# 02_Inputs_1-9.net
KiCad netlist of a schematic drawn in Altium Designer
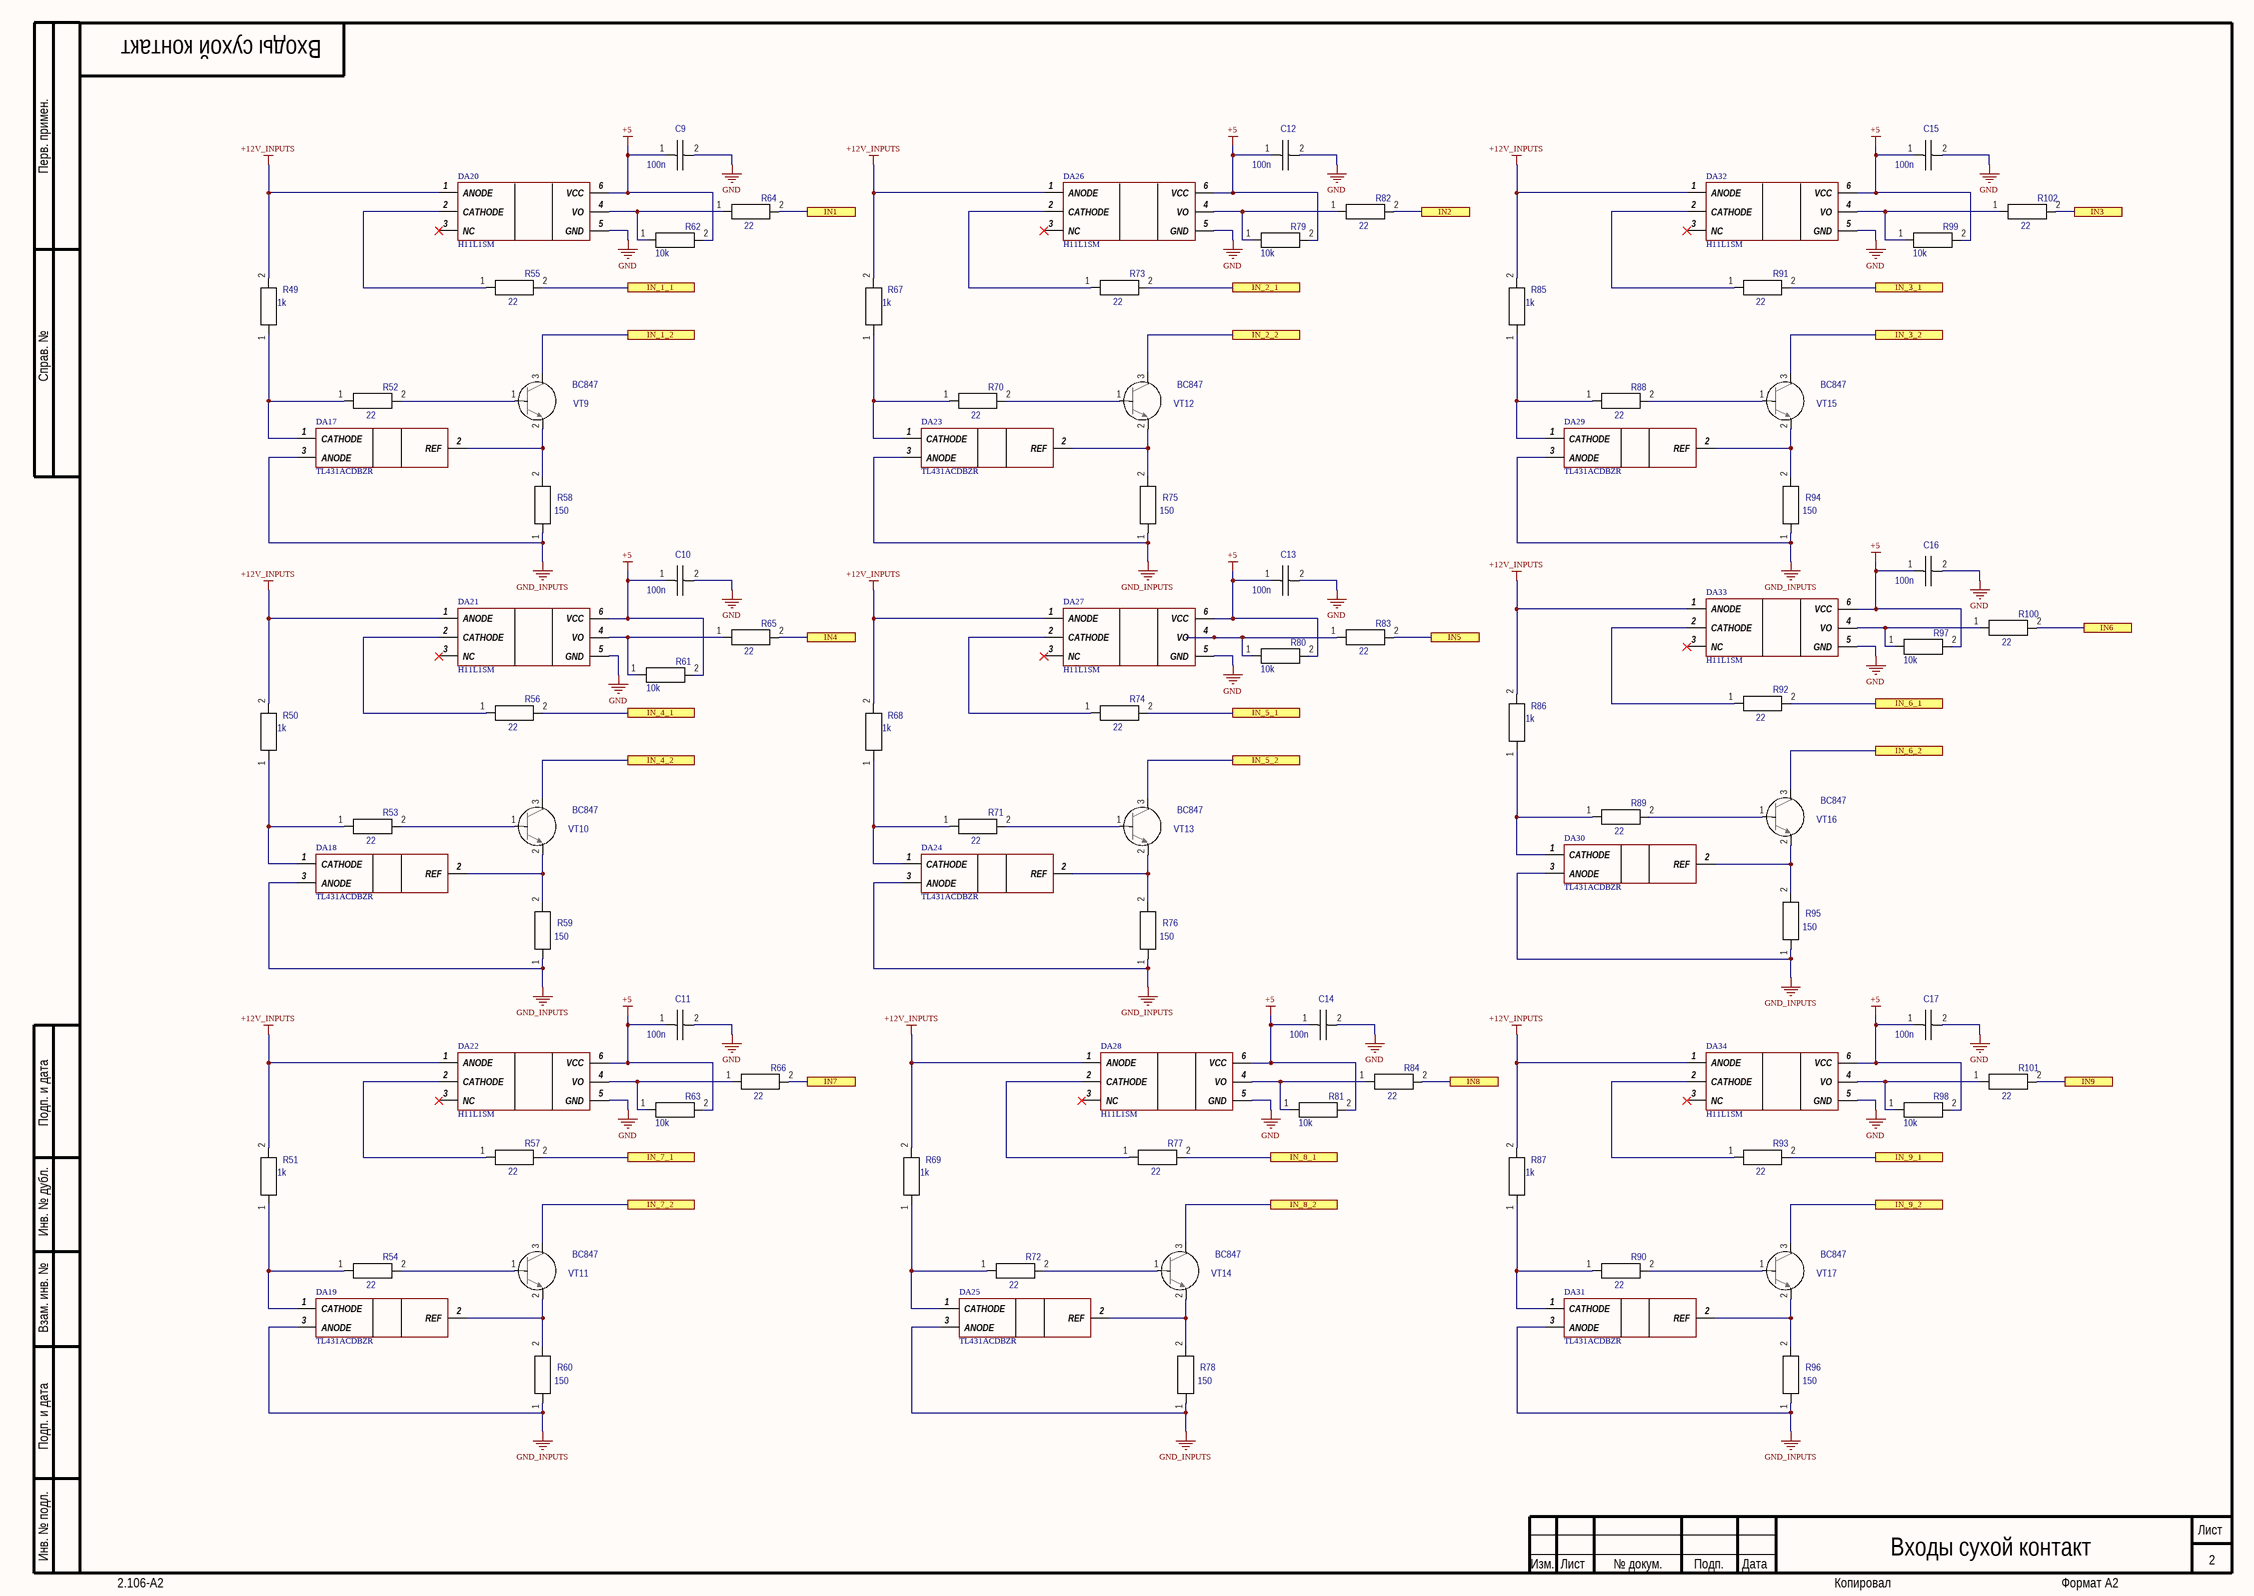
[diagram p0: 02_Inputs_1-9.SchDoc]

(export (version "E")
  (design (tool "Eeschema 10.0.6"))
  (components
    (comp (ref "C9")
      (value "100n")
      (footprint "C0603")
      (fields
        (field (name "PART NUMBER") "GRM188R71C104KA01D")
        (field (name "TOLERANCE") "±10%")
        (field (name "MANUFACTURER") "Murata Manufacturing")
      )
      (libsource (lib "AccessLibrary") (part "Capacitor"))
    )
    (comp (ref "C10")
      (value "100n")
      (footprint "C0603")
      (fields
        (field (name "PART NUMBER") "GRM188R71C104KA01D")
        (field (name "TOLERANCE") "±10%")
        (field (name "MANUFACTURER") "Murata Manufacturing")
      )
      (libsource (lib "AccessLibrary") (part "Capacitor"))
    )
    (comp (ref "C11")
      (value "100n")
      (footprint "C0603")
      (fields
        (field (name "PART NUMBER") "GRM188R71C104KA01D")
        (field (name "TOLERANCE") "±10%")
        (field (name "MANUFACTURER") "Murata Manufacturing")
      )
      (libsource (lib "AccessLibrary") (part "Capacitor"))
    )
    (comp (ref "C12")
      (value "100n")
      (footprint "C0603")
      (fields
        (field (name "PART NUMBER") "GRM188R71C104KA01D")
        (field (name "TOLERANCE") "±10%")
        (field (name "MANUFACTURER") "Murata Manufacturing")
      )
      (libsource (lib "AccessLibrary") (part "Capacitor"))
    )
    (comp (ref "C13")
      (value "100n")
      (footprint "C0603")
      (fields
        (field (name "PART NUMBER") "GRM188R71C104KA01D")
        (field (name "TOLERANCE") "±10%")
        (field (name "MANUFACTURER") "Murata Manufacturing")
      )
      (libsource (lib "AccessLibrary") (part "Capacitor"))
    )
    (comp (ref "C14")
      (value "100n")
      (footprint "C0603")
      (fields
        (field (name "PART NUMBER") "GRM188R71C104KA01D")
        (field (name "TOLERANCE") "±10%")
        (field (name "MANUFACTURER") "Murata Manufacturing")
      )
      (libsource (lib "AccessLibrary") (part "Capacitor"))
    )
    (comp (ref "C15")
      (value "100n")
      (footprint "C0603")
      (fields
        (field (name "PART NUMBER") "GRM188R71C104KA01D")
        (field (name "TOLERANCE") "±10%")
        (field (name "MANUFACTURER") "Murata Manufacturing")
      )
      (libsource (lib "AccessLibrary") (part "Capacitor"))
    )
    (comp (ref "C16")
      (value "100n")
      (footprint "C0603")
      (fields
        (field (name "PART NUMBER") "GRM188R71C104KA01D")
        (field (name "TOLERANCE") "±10%")
        (field (name "MANUFACTURER") "Murata Manufacturing")
      )
      (libsource (lib "AccessLibrary") (part "Capacitor"))
    )
    (comp (ref "C17")
      (value "100n")
      (footprint "C0603")
      (fields
        (field (name "PART NUMBER") "GRM188R71C104KA01D")
        (field (name "TOLERANCE") "±10%")
        (field (name "MANUFACTURER") "Murata Manufacturing")
      )
      (libsource (lib "AccessLibrary") (part "Capacitor"))
    )
    (comp (ref "DA17")
      (value "TL431ACDBZR")
      (footprint "board:SOT95P237X112-3N")
      (description "Integrated Circuit")
      (fields (field (name "MOUSER PART NUMBER") "595-TL431ACDBZR"))
      (libsource (lib "board") (part "TL431ACDBZR"))
    )
    (comp (ref "DA18")
      (value "TL431ACDBZR")
      (footprint "board:SOT95P237X112-3N")
      (description "Integrated Circuit")
      (fields (field (name "MOUSER PART NUMBER") "595-TL431ACDBZR"))
      (libsource (lib "board") (part "TL431ACDBZR"))
    )
    (comp (ref "DA19")
      (value "TL431ACDBZR")
      (footprint "board:SOT95P237X112-3N")
      (description "Integrated Circuit")
      (fields (field (name "MOUSER PART NUMBER") "595-TL431ACDBZR"))
      (libsource (lib "board") (part "TL431ACDBZR"))
    )
    (comp (ref "DA20")
      (value "H11L1SM")
      (footprint "board:SOP254P1030X460-6N")
      (description "Integrated Circuit")
      (libsource (lib "board") (part "H11L1SM"))
    )
    (comp (ref "DA21")
      (value "H11L1SM")
      (footprint "board:SOP254P1030X460-6N")
      (description "Integrated Circuit")
      (libsource (lib "board") (part "H11L1SM"))
    )
    (comp (ref "DA22")
      (value "H11L1SM")
      (footprint "board:SOP254P1030X460-6N")
      (description "Integrated Circuit")
      (libsource (lib "board") (part "H11L1SM"))
    )
    (comp (ref "DA23")
      (value "TL431ACDBZR")
      (footprint "board:SOT95P237X112-3N")
      (description "Integrated Circuit")
      (fields (field (name "MOUSER PART NUMBER") "595-TL431ACDBZR"))
      (libsource (lib "board") (part "TL431ACDBZR"))
    )
    (comp (ref "DA24")
      (value "TL431ACDBZR")
      (footprint "board:SOT95P237X112-3N")
      (description "Integrated Circuit")
      (fields (field (name "MOUSER PART NUMBER") "595-TL431ACDBZR"))
      (libsource (lib "board") (part "TL431ACDBZR"))
    )
    (comp (ref "DA25")
      (value "TL431ACDBZR")
      (footprint "board:SOT95P237X112-3N")
      (description "Integrated Circuit")
      (fields (field (name "MOUSER PART NUMBER") "595-TL431ACDBZR"))
      (libsource (lib "board") (part "TL431ACDBZR"))
    )
    (comp (ref "DA26")
      (value "H11L1SM")
      (footprint "board:SOP254P1030X460-6N")
      (description "Integrated Circuit")
      (libsource (lib "board") (part "H11L1SM"))
    )
    (comp (ref "DA27")
      (value "H11L1SM")
      (footprint "board:SOP254P1030X460-6N")
      (description "Integrated Circuit")
      (libsource (lib "board") (part "H11L1SM"))
    )
    (comp (ref "DA28")
      (value "H11L1SM")
      (footprint "board:SOP254P1030X460-6N")
      (description "Integrated Circuit")
      (libsource (lib "board") (part "H11L1SM"))
    )
    (comp (ref "DA29")
      (value "TL431ACDBZR")
      (footprint "board:SOT95P237X112-3N")
      (description "Integrated Circuit")
      (fields (field (name "MOUSER PART NUMBER") "595-TL431ACDBZR"))
      (libsource (lib "board") (part "TL431ACDBZR"))
    )
    (comp (ref "DA30")
      (value "TL431ACDBZR")
      (footprint "board:SOT95P237X112-3N")
      (description "Integrated Circuit")
      (fields (field (name "MOUSER PART NUMBER") "595-TL431ACDBZR"))
      (libsource (lib "board") (part "TL431ACDBZR"))
    )
    (comp (ref "DA31")
      (value "TL431ACDBZR")
      (footprint "board:SOT95P237X112-3N")
      (description "Integrated Circuit")
      (fields (field (name "MOUSER PART NUMBER") "595-TL431ACDBZR"))
      (libsource (lib "board") (part "TL431ACDBZR"))
    )
    (comp (ref "DA32")
      (value "H11L1SM")
      (footprint "board:SOP254P1030X460-6N")
      (description "Integrated Circuit")
      (libsource (lib "board") (part "H11L1SM"))
    )
    (comp (ref "DA33")
      (value "H11L1SM")
      (footprint "board:SOP254P1030X460-6N")
      (description "Integrated Circuit")
      (libsource (lib "board") (part "H11L1SM"))
    )
    (comp (ref "DA34")
      (value "H11L1SM")
      (footprint "board:SOP254P1030X460-6N")
      (description "Integrated Circuit")
      (libsource (lib "board") (part "H11L1SM"))
    )
    (comp (ref "R49")
      (value "1k")
      (footprint "RESC1608N")
      (fields
        (field (name "PART NUMBER") "RC0603FK-071KL")
        (field (name "TOLERANCE") "±1%")
        (field (name "MANUFACTURER") "Тайвань")
      )
      (libsource (lib "AccessLibrary") (part "Resistor"))
    )
    (comp (ref "R50")
      (value "1k")
      (footprint "RESC1608N")
      (fields
        (field (name "PART NUMBER") "RC0603FK-071KL")
        (field (name "TOLERANCE") "±1%")
        (field (name "MANUFACTURER") "Тайвань")
      )
      (libsource (lib "AccessLibrary") (part "Resistor"))
    )
    (comp (ref "R51")
      (value "1k")
      (footprint "RESC1608N")
      (fields
        (field (name "PART NUMBER") "RC0603FK-071KL")
        (field (name "TOLERANCE") "±1%")
        (field (name "MANUFACTURER") "Тайвань")
      )
      (libsource (lib "AccessLibrary") (part "Resistor"))
    )
    (comp (ref "R52")
      (value "22")
      (footprint "RESC1608N")
      (fields
        (field (name "PART NUMBER") "RC0603FK-0722RL")
        (field (name "TOLERANCE") "±1%")
        (field (name "MANUFACTURER") "Тайвань")
      )
      (libsource (lib "AccessLibrary") (part "Resistor"))
    )
    (comp (ref "R53")
      (value "22")
      (footprint "RESC1608N")
      (fields
        (field (name "PART NUMBER") "RC0603FK-0722RL")
        (field (name "TOLERANCE") "±1%")
        (field (name "MANUFACTURER") "Тайвань")
      )
      (libsource (lib "AccessLibrary") (part "Resistor"))
    )
    (comp (ref "R54")
      (value "22")
      (footprint "RESC1608N")
      (fields
        (field (name "PART NUMBER") "RC0603FK-0722RL")
        (field (name "TOLERANCE") "±1%")
        (field (name "MANUFACTURER") "Тайвань")
      )
      (libsource (lib "AccessLibrary") (part "Resistor"))
    )
    (comp (ref "R55")
      (value "22")
      (footprint "RESC1608N")
      (fields
        (field (name "PART NUMBER") "RC0603FK-0722RL")
        (field (name "TOLERANCE") "±1%")
        (field (name "MANUFACTURER") "Тайвань")
      )
      (libsource (lib "AccessLibrary") (part "Resistor"))
    )
    (comp (ref "R56")
      (value "22")
      (footprint "RESC1608N")
      (fields
        (field (name "PART NUMBER") "RC0603FK-0722RL")
        (field (name "TOLERANCE") "±1%")
        (field (name "MANUFACTURER") "Тайвань")
      )
      (libsource (lib "AccessLibrary") (part "Resistor"))
    )
    (comp (ref "R57")
      (value "22")
      (footprint "RESC1608N")
      (fields
        (field (name "PART NUMBER") "RC0603FK-0722RL")
        (field (name "TOLERANCE") "±1%")
        (field (name "MANUFACTURER") "Тайвань")
      )
      (libsource (lib "AccessLibrary") (part "Resistor"))
    )
    (comp (ref "R58")
      (value "150")
      (footprint "RESC1608N")
      (fields
        (field (name "PART NUMBER") "RC0603FK-07150RL")
        (field (name "TOLERANCE") "±1%")
        (field (name "MANUFACTURER") "Тайвань")
      )
      (libsource (lib "AccessLibrary") (part "Resistor"))
    )
    (comp (ref "R59")
      (value "150")
      (footprint "RESC1608N")
      (fields
        (field (name "PART NUMBER") "RC0603FK-07150RL")
        (field (name "TOLERANCE") "±1%")
        (field (name "MANUFACTURER") "Тайвань")
      )
      (libsource (lib "AccessLibrary") (part "Resistor"))
    )
    (comp (ref "R60")
      (value "150")
      (footprint "RESC1608N")
      (fields
        (field (name "PART NUMBER") "RC0603FK-07150RL")
        (field (name "TOLERANCE") "±1%")
        (field (name "MANUFACTURER") "Тайвань")
      )
      (libsource (lib "AccessLibrary") (part "Resistor"))
    )
    (comp (ref "R61")
      (value "10k")
      (footprint "RESC1608N")
      (fields
        (field (name "PART NUMBER") "RC0603FR-0710KL")
        (field (name "TOLERANCE") "±1%")
        (field (name "MANUFACTURER") "Тайвань")
      )
      (libsource (lib "AccessLibrary") (part "Resistor"))
    )
    (comp (ref "R62")
      (value "10k")
      (footprint "RESC1608N")
      (fields
        (field (name "PART NUMBER") "RC0603FR-0710KL")
        (field (name "TOLERANCE") "±1%")
        (field (name "MANUFACTURER") "Тайвань")
      )
      (libsource (lib "AccessLibrary") (part "Resistor"))
    )
    (comp (ref "R63")
      (value "10k")
      (footprint "RESC1608N")
      (fields
        (field (name "PART NUMBER") "RC0603FR-0710KL")
        (field (name "TOLERANCE") "±1%")
        (field (name "MANUFACTURER") "Тайвань")
      )
      (libsource (lib "AccessLibrary") (part "Resistor"))
    )
    (comp (ref "R64")
      (value "22")
      (footprint "RESC1608N")
      (fields
        (field (name "PART NUMBER") "RC0603FK-0722RL")
        (field (name "TOLERANCE") "±1%")
        (field (name "MANUFACTURER") "Тайвань")
      )
      (libsource (lib "AccessLibrary") (part "Resistor"))
    )
    (comp (ref "R65")
      (value "22")
      (footprint "RESC1608N")
      (fields
        (field (name "PART NUMBER") "RC0603FK-0722RL")
        (field (name "TOLERANCE") "±1%")
        (field (name "MANUFACTURER") "Тайвань")
      )
      (libsource (lib "AccessLibrary") (part "Resistor"))
    )
    (comp (ref "R66")
      (value "22")
      (footprint "RESC1608N")
      (fields
        (field (name "PART NUMBER") "RC0603FK-0722RL")
        (field (name "TOLERANCE") "±1%")
        (field (name "MANUFACTURER") "Тайвань")
      )
      (libsource (lib "AccessLibrary") (part "Resistor"))
    )
    (comp (ref "R67")
      (value "1k")
      (footprint "RESC1608N")
      (fields
        (field (name "PART NUMBER") "RC0603FK-071KL")
        (field (name "TOLERANCE") "±1%")
        (field (name "MANUFACTURER") "Тайвань")
      )
      (libsource (lib "AccessLibrary") (part "Resistor"))
    )
    (comp (ref "R68")
      (value "1k")
      (footprint "RESC1608N")
      (fields
        (field (name "PART NUMBER") "RC0603FK-071KL")
        (field (name "TOLERANCE") "±1%")
        (field (name "MANUFACTURER") "Тайвань")
      )
      (libsource (lib "AccessLibrary") (part "Resistor"))
    )
    (comp (ref "R69")
      (value "1k")
      (footprint "RESC1608N")
      (fields
        (field (name "PART NUMBER") "RC0603FK-071KL")
        (field (name "TOLERANCE") "±1%")
        (field (name "MANUFACTURER") "Тайвань")
      )
      (libsource (lib "AccessLibrary") (part "Resistor"))
    )
    (comp (ref "R70")
      (value "22")
      (footprint "RESC1608N")
      (fields
        (field (name "PART NUMBER") "RC0603FK-0722RL")
        (field (name "TOLERANCE") "±1%")
        (field (name "MANUFACTURER") "Тайвань")
      )
      (libsource (lib "AccessLibrary") (part "Resistor"))
    )
    (comp (ref "R71")
      (value "22")
      (footprint "RESC1608N")
      (fields
        (field (name "PART NUMBER") "RC0603FK-0722RL")
        (field (name "TOLERANCE") "±1%")
        (field (name "MANUFACTURER") "Тайвань")
      )
      (libsource (lib "AccessLibrary") (part "Resistor"))
    )
    (comp (ref "R72")
      (value "22")
      (footprint "RESC1608N")
      (fields
        (field (name "PART NUMBER") "RC0603FK-0722RL")
        (field (name "TOLERANCE") "±1%")
        (field (name "MANUFACTURER") "Тайвань")
      )
      (libsource (lib "AccessLibrary") (part "Resistor"))
    )
    (comp (ref "R73")
      (value "22")
      (footprint "RESC1608N")
      (fields
        (field (name "PART NUMBER") "RC0603FK-0722RL")
        (field (name "TOLERANCE") "±1%")
        (field (name "MANUFACTURER") "Тайвань")
      )
      (libsource (lib "AccessLibrary") (part "Resistor"))
    )
    (comp (ref "R74")
      (value "22")
      (footprint "RESC1608N")
      (fields
        (field (name "PART NUMBER") "RC0603FK-0722RL")
        (field (name "TOLERANCE") "±1%")
        (field (name "MANUFACTURER") "Тайвань")
      )
      (libsource (lib "AccessLibrary") (part "Resistor"))
    )
    (comp (ref "R75")
      (value "150")
      (footprint "RESC1608N")
      (fields
        (field (name "PART NUMBER") "RC0603FK-07150RL")
        (field (name "TOLERANCE") "±1%")
        (field (name "MANUFACTURER") "Тайвань")
      )
      (libsource (lib "AccessLibrary") (part "Resistor"))
    )
    (comp (ref "R76")
      (value "150")
      (footprint "RESC1608N")
      (fields
        (field (name "PART NUMBER") "RC0603FK-07150RL")
        (field (name "TOLERANCE") "±1%")
        (field (name "MANUFACTURER") "Тайвань")
      )
      (libsource (lib "AccessLibrary") (part "Resistor"))
    )
    (comp (ref "R77")
      (value "22")
      (footprint "RESC1608N")
      (fields
        (field (name "PART NUMBER") "RC0603FK-0722RL")
        (field (name "TOLERANCE") "±1%")
        (field (name "MANUFACTURER") "Тайвань")
      )
      (libsource (lib "AccessLibrary") (part "Resistor"))
    )
    (comp (ref "R78")
      (value "150")
      (footprint "RESC1608N")
      (fields
        (field (name "PART NUMBER") "RC0603FK-07150RL")
        (field (name "TOLERANCE") "±1%")
        (field (name "MANUFACTURER") "Тайвань")
      )
      (libsource (lib "AccessLibrary") (part "Resistor"))
    )
    (comp (ref "R79")
      (value "10k")
      (footprint "RESC1608N")
      (fields
        (field (name "PART NUMBER") "RC0603FR-0710KL")
        (field (name "TOLERANCE") "±1%")
        (field (name "MANUFACTURER") "Тайвань")
      )
      (libsource (lib "AccessLibrary") (part "Resistor"))
    )
    (comp (ref "R80")
      (value "10k")
      (footprint "RESC1608N")
      (fields
        (field (name "PART NUMBER") "RC0603FR-0710KL")
        (field (name "TOLERANCE") "±1%")
        (field (name "MANUFACTURER") "Тайвань")
      )
      (libsource (lib "AccessLibrary") (part "Resistor"))
    )
    (comp (ref "R81")
      (value "10k")
      (footprint "RESC1608N")
      (fields
        (field (name "PART NUMBER") "RC0603FR-0710KL")
        (field (name "TOLERANCE") "±1%")
        (field (name "MANUFACTURER") "Тайвань")
      )
      (libsource (lib "AccessLibrary") (part "Resistor"))
    )
    (comp (ref "R82")
      (value "22")
      (footprint "RESC1608N")
      (fields
        (field (name "PART NUMBER") "RC0603FK-0722RL")
        (field (name "TOLERANCE") "±1%")
        (field (name "MANUFACTURER") "Тайвань")
      )
      (libsource (lib "AccessLibrary") (part "Resistor"))
    )
    (comp (ref "R83")
      (value "22")
      (footprint "RESC1608N")
      (fields
        (field (name "PART NUMBER") "RC0603FK-0722RL")
        (field (name "TOLERANCE") "±1%")
        (field (name "MANUFACTURER") "Тайвань")
      )
      (libsource (lib "AccessLibrary") (part "Resistor"))
    )
    (comp (ref "R84")
      (value "22")
      (footprint "RESC1608N")
      (fields
        (field (name "PART NUMBER") "RC0603FK-0722RL")
        (field (name "TOLERANCE") "±1%")
        (field (name "MANUFACTURER") "Тайвань")
      )
      (libsource (lib "AccessLibrary") (part "Resistor"))
    )
    (comp (ref "R85")
      (value "1k")
      (footprint "RESC1608N")
      (fields
        (field (name "PART NUMBER") "RC0603FK-071KL")
        (field (name "TOLERANCE") "±1%")
        (field (name "MANUFACTURER") "Тайвань")
      )
      (libsource (lib "AccessLibrary") (part "Resistor"))
    )
    (comp (ref "R86")
      (value "1k")
      (footprint "RESC1608N")
      (fields
        (field (name "PART NUMBER") "RC0603FK-071KL")
        (field (name "TOLERANCE") "±1%")
        (field (name "MANUFACTURER") "Тайвань")
      )
      (libsource (lib "AccessLibrary") (part "Resistor"))
    )
    (comp (ref "R87")
      (value "1k")
      (footprint "RESC1608N")
      (fields
        (field (name "PART NUMBER") "RC0603FK-071KL")
        (field (name "TOLERANCE") "±1%")
        (field (name "MANUFACTURER") "Тайвань")
      )
      (libsource (lib "AccessLibrary") (part "Resistor"))
    )
    (comp (ref "R88")
      (value "22")
      (footprint "RESC1608N")
      (fields
        (field (name "PART NUMBER") "RC0603FK-0722RL")
        (field (name "TOLERANCE") "±1%")
        (field (name "MANUFACTURER") "Тайвань")
      )
      (libsource (lib "AccessLibrary") (part "Resistor"))
    )
    (comp (ref "R89")
      (value "22")
      (footprint "RESC1608N")
      (fields
        (field (name "PART NUMBER") "RC0603FK-0722RL")
        (field (name "TOLERANCE") "±1%")
        (field (name "MANUFACTURER") "Тайвань")
      )
      (libsource (lib "AccessLibrary") (part "Resistor"))
    )
    (comp (ref "R90")
      (value "22")
      (footprint "RESC1608N")
      (fields
        (field (name "PART NUMBER") "RC0603FK-0722RL")
        (field (name "TOLERANCE") "±1%")
        (field (name "MANUFACTURER") "Тайвань")
      )
      (libsource (lib "AccessLibrary") (part "Resistor"))
    )
    (comp (ref "R91")
      (value "22")
      (footprint "RESC1608N")
      (fields
        (field (name "PART NUMBER") "RC0603FK-0722RL")
        (field (name "TOLERANCE") "±1%")
        (field (name "MANUFACTURER") "Тайвань")
      )
      (libsource (lib "AccessLibrary") (part "Resistor"))
    )
    (comp (ref "R92")
      (value "22")
      (footprint "RESC1608N")
      (fields
        (field (name "PART NUMBER") "RC0603FK-0722RL")
        (field (name "TOLERANCE") "±1%")
        (field (name "MANUFACTURER") "Тайвань")
      )
      (libsource (lib "AccessLibrary") (part "Resistor"))
    )
    (comp (ref "R93")
      (value "22")
      (footprint "RESC1608N")
      (fields
        (field (name "PART NUMBER") "RC0603FK-0722RL")
        (field (name "TOLERANCE") "±1%")
        (field (name "MANUFACTURER") "Тайвань")
      )
      (libsource (lib "AccessLibrary") (part "Resistor"))
    )
    (comp (ref "R94")
      (value "150")
      (footprint "RESC1608N")
      (fields
        (field (name "PART NUMBER") "RC0603FK-07150RL")
        (field (name "TOLERANCE") "±1%")
        (field (name "MANUFACTURER") "Тайвань")
      )
      (libsource (lib "AccessLibrary") (part "Resistor"))
    )
    (comp (ref "R95")
      (value "150")
      (footprint "RESC1608N")
      (fields
        (field (name "PART NUMBER") "RC0603FK-07150RL")
        (field (name "TOLERANCE") "±1%")
        (field (name "MANUFACTURER") "Тайвань")
      )
      (libsource (lib "AccessLibrary") (part "Resistor"))
    )
    (comp (ref "R96")
      (value "150")
      (footprint "RESC1608N")
      (fields
        (field (name "PART NUMBER") "RC0603FK-07150RL")
        (field (name "TOLERANCE") "±1%")
        (field (name "MANUFACTURER") "Тайвань")
      )
      (libsource (lib "AccessLibrary") (part "Resistor"))
    )
    (comp (ref "R97")
      (value "10k")
      (footprint "RESC1608N")
      (fields
        (field (name "PART NUMBER") "RC0603FR-0710KL")
        (field (name "TOLERANCE") "±1%")
        (field (name "MANUFACTURER") "Тайвань")
      )
      (libsource (lib "AccessLibrary") (part "Resistor"))
    )
    (comp (ref "R98")
      (value "10k")
      (footprint "RESC1608N")
      (fields
        (field (name "PART NUMBER") "RC0603FR-0710KL")
        (field (name "TOLERANCE") "±1%")
        (field (name "MANUFACTURER") "Тайвань")
      )
      (libsource (lib "AccessLibrary") (part "Resistor"))
    )
    (comp (ref "R99")
      (value "10k")
      (footprint "RESC1608N")
      (fields
        (field (name "PART NUMBER") "RC0603FR-0710KL")
        (field (name "TOLERANCE") "±1%")
        (field (name "MANUFACTURER") "Тайвань")
      )
      (libsource (lib "AccessLibrary") (part "Resistor"))
    )
    (comp (ref "R100")
      (value "22")
      (footprint "RESC1608N")
      (fields
        (field (name "PART NUMBER") "RC0603FK-0722RL")
        (field (name "TOLERANCE") "±1%")
        (field (name "MANUFACTURER") "Тайвань")
      )
      (libsource (lib "AccessLibrary") (part "Resistor"))
    )
    (comp (ref "R101")
      (value "22")
      (footprint "RESC1608N")
      (fields
        (field (name "PART NUMBER") "RC0603FK-0722RL")
        (field (name "TOLERANCE") "±1%")
        (field (name "MANUFACTURER") "Тайвань")
      )
      (libsource (lib "AccessLibrary") (part "Resistor"))
    )
    (comp (ref "R102")
      (value "22")
      (footprint "RESC1608N")
      (fields
        (field (name "PART NUMBER") "RC0603FK-0722RL")
        (field (name "TOLERANCE") "±1%")
        (field (name "MANUFACTURER") "Тайвань")
      )
      (libsource (lib "AccessLibrary") (part "Resistor"))
    )
    (comp (ref "VT9")
      (value "BC847")
      (footprint "SOT23-3N")
      (fields (field (name "COM") "BC847") (field (name "MANUFACTURER") "NXP Semiconductor"))
      (libsource (lib "AccessLibrary") (part "Transistor_npn_1b-2e-3c"))
    )
    (comp (ref "VT10")
      (value "BC847")
      (footprint "SOT23-3N")
      (fields (field (name "COM") "BC847") (field (name "MANUFACTURER") "NXP Semiconductor"))
      (libsource (lib "AccessLibrary") (part "Transistor_npn_1b-2e-3c"))
    )
    (comp (ref "VT11")
      (value "BC847")
      (footprint "SOT23-3N")
      (fields (field (name "COM") "BC847") (field (name "MANUFACTURER") "NXP Semiconductor"))
      (libsource (lib "AccessLibrary") (part "Transistor_npn_1b-2e-3c"))
    )
    (comp (ref "VT12")
      (value "BC847")
      (footprint "SOT23-3N")
      (fields (field (name "COM") "BC847") (field (name "MANUFACTURER") "NXP Semiconductor"))
      (libsource (lib "AccessLibrary") (part "Transistor_npn_1b-2e-3c"))
    )
    (comp (ref "VT13")
      (value "BC847")
      (footprint "SOT23-3N")
      (fields (field (name "COM") "BC847") (field (name "MANUFACTURER") "NXP Semiconductor"))
      (libsource (lib "AccessLibrary") (part "Transistor_npn_1b-2e-3c"))
    )
    (comp (ref "VT14")
      (value "BC847")
      (footprint "SOT23-3N")
      (fields (field (name "COM") "BC847") (field (name "MANUFACTURER") "NXP Semiconductor"))
      (libsource (lib "AccessLibrary") (part "Transistor_npn_1b-2e-3c"))
    )
    (comp (ref "VT15")
      (value "BC847")
      (footprint "SOT23-3N")
      (fields (field (name "COM") "BC847") (field (name "MANUFACTURER") "NXP Semiconductor"))
      (libsource (lib "AccessLibrary") (part "Transistor_npn_1b-2e-3c"))
    )
    (comp (ref "VT16")
      (value "BC847")
      (footprint "SOT23-3N")
      (fields (field (name "COM") "BC847") (field (name "MANUFACTURER") "NXP Semiconductor"))
      (libsource (lib "AccessLibrary") (part "Transistor_npn_1b-2e-3c"))
    )
    (comp (ref "VT17")
      (value "BC847")
      (footprint "SOT23-3N")
      (fields (field (name "COM") "BC847") (field (name "MANUFACTURER") "NXP Semiconductor"))
      (libsource (lib "AccessLibrary") (part "Transistor_npn_1b-2e-3c"))
    )
  )
  (nets
    (net (code "1") (name "+5") (class "Default")
      (node (ref "C10") (pin "1") (pinfunction "1_1") (pintype "passive"))
      (node (ref "C11") (pin "1") (pinfunction "1_1") (pintype "passive"))
      (node (ref "C12") (pin "1") (pinfunction "1_1") (pintype "passive"))
      (node (ref "C13") (pin "1") (pinfunction "1_1") (pintype "passive"))
      (node (ref "C14") (pin "1") (pinfunction "1_1") (pintype "passive"))
      (node (ref "C15") (pin "1") (pinfunction "1_1") (pintype "passive"))
      (node (ref "C16") (pin "1") (pinfunction "1_1") (pintype "passive"))
      (node (ref "C17") (pin "1") (pinfunction "1_1") (pintype "passive"))
      (node (ref "C9") (pin "1") (pinfunction "1_1") (pintype "passive"))
      (node (ref "DA20") (pin "6") (pinfunction "VCC_6") (pintype "passive"))
      (node (ref "DA21") (pin "6") (pinfunction "VCC_6") (pintype "passive"))
      (node (ref "DA22") (pin "6") (pinfunction "VCC_6") (pintype "passive"))
      (node (ref "DA26") (pin "6") (pinfunction "VCC_6") (pintype "passive"))
      (node (ref "DA27") (pin "6") (pinfunction "VCC_6") (pintype "passive"))
      (node (ref "DA28") (pin "6") (pinfunction "VCC_6") (pintype "passive"))
      (node (ref "DA32") (pin "6") (pinfunction "VCC_6") (pintype "passive"))
      (node (ref "DA33") (pin "6") (pinfunction "VCC_6") (pintype "passive"))
      (node (ref "DA34") (pin "6") (pinfunction "VCC_6") (pintype "passive"))
      (node (ref "R61") (pin "2") (pinfunction "2_2") (pintype "passive"))
      (node (ref "R62") (pin "2") (pinfunction "2_2") (pintype "passive"))
      (node (ref "R63") (pin "2") (pinfunction "2_2") (pintype "passive"))
      (node (ref "R79") (pin "2") (pinfunction "2_2") (pintype "passive"))
      (node (ref "R80") (pin "2") (pinfunction "2_2") (pintype "passive"))
      (node (ref "R81") (pin "2") (pinfunction "2_2") (pintype "passive"))
      (node (ref "R97") (pin "2") (pinfunction "2_2") (pintype "passive"))
      (node (ref "R98") (pin "2") (pinfunction "2_2") (pintype "passive"))
      (node (ref "R99") (pin "2") (pinfunction "2_2") (pintype "passive"))
    )
    (net (code "2") (name "+12V_INPUTS") (class "Default")
      (node (ref "DA20") (pin "1") (pinfunction "ANODE_1") (pintype "passive"))
      (node (ref "DA21") (pin "1") (pinfunction "ANODE_1") (pintype "passive"))
      (node (ref "DA22") (pin "1") (pinfunction "ANODE_1") (pintype "passive"))
      (node (ref "DA26") (pin "1") (pinfunction "ANODE_1") (pintype "passive"))
      (node (ref "DA27") (pin "1") (pinfunction "ANODE_1") (pintype "passive"))
      (node (ref "DA28") (pin "1") (pinfunction "ANODE_1") (pintype "passive"))
      (node (ref "DA32") (pin "1") (pinfunction "ANODE_1") (pintype "passive"))
      (node (ref "DA33") (pin "1") (pinfunction "ANODE_1") (pintype "passive"))
      (node (ref "DA34") (pin "1") (pinfunction "ANODE_1") (pintype "passive"))
      (node (ref "R49") (pin "2") (pinfunction "2_2") (pintype "passive"))
      (node (ref "R50") (pin "2") (pinfunction "2_2") (pintype "passive"))
      (node (ref "R51") (pin "2") (pinfunction "2_2") (pintype "passive"))
      (node (ref "R67") (pin "2") (pinfunction "2_2") (pintype "passive"))
      (node (ref "R68") (pin "2") (pinfunction "2_2") (pintype "passive"))
      (node (ref "R69") (pin "2") (pinfunction "2_2") (pintype "passive"))
      (node (ref "R85") (pin "2") (pinfunction "2_2") (pintype "passive"))
      (node (ref "R86") (pin "2") (pinfunction "2_2") (pintype "passive"))
      (node (ref "R87") (pin "2") (pinfunction "2_2") (pintype "passive"))
    )
    (net (code "3") (name "/IN1") (class "Default")
      (node (ref "R64") (pin "2") (pinfunction "2_2") (pintype "passive"))
    )
    (net (code "4") (name "/IN2") (class "Default")
      (node (ref "R82") (pin "2") (pinfunction "2_2") (pintype "passive"))
    )
    (net (code "5") (name "/IN3") (class "Default")
      (node (ref "R102") (pin "2") (pinfunction "2_2") (pintype "passive"))
    )
    (net (code "6") (name "/IN4") (class "Default")
      (node (ref "R65") (pin "2") (pinfunction "2_2") (pintype "passive"))
    )
    (net (code "7") (name "/IN5") (class "Default")
      (node (ref "R83") (pin "2") (pinfunction "2_2") (pintype "passive"))
    )
    (net (code "8") (name "/IN6") (class "Default")
      (node (ref "R100") (pin "2") (pinfunction "2_2") (pintype "passive"))
    )
    (net (code "9") (name "/IN7") (class "Default")
      (node (ref "R66") (pin "2") (pinfunction "2_2") (pintype "passive"))
    )
    (net (code "10") (name "/IN8") (class "Default")
      (node (ref "R84") (pin "2") (pinfunction "2_2") (pintype "passive"))
    )
    (net (code "11") (name "/IN9") (class "Default")
      (node (ref "R101") (pin "2") (pinfunction "2_2") (pintype "passive"))
    )
    (net (code "12") (name "/IN_1_1") (class "Default")
      (node (ref "R55") (pin "2") (pinfunction "2_2") (pintype "passive"))
    )
    (net (code "13") (name "/IN_1_2") (class "Default")
      (node (ref "VT9") (pin "3") (pinfunction "3_3") (pintype "passive"))
    )
    (net (code "14") (name "/IN_2_1") (class "Default")
      (node (ref "R73") (pin "2") (pinfunction "2_2") (pintype "passive"))
    )
    (net (code "15") (name "/IN_2_2") (class "Default")
      (node (ref "VT12") (pin "3") (pinfunction "3_3") (pintype "passive"))
    )
    (net (code "16") (name "/IN_3_1") (class "Default")
      (node (ref "R91") (pin "2") (pinfunction "2_2") (pintype "passive"))
    )
    (net (code "17") (name "/IN_3_2") (class "Default")
      (node (ref "VT15") (pin "3") (pinfunction "3_3") (pintype "passive"))
    )
    (net (code "18") (name "/IN_4_1") (class "Default")
      (node (ref "R56") (pin "2") (pinfunction "2_2") (pintype "passive"))
    )
    (net (code "19") (name "/IN_4_2") (class "Default")
      (node (ref "VT10") (pin "3") (pinfunction "3_3") (pintype "passive"))
    )
    (net (code "20") (name "/IN_5_1") (class "Default")
      (node (ref "R74") (pin "2") (pinfunction "2_2") (pintype "passive"))
    )
    (net (code "21") (name "/IN_5_2") (class "Default")
      (node (ref "VT13") (pin "3") (pinfunction "3_3") (pintype "passive"))
    )
    (net (code "22") (name "/IN_6_1") (class "Default")
      (node (ref "R92") (pin "2") (pinfunction "2_2") (pintype "passive"))
    )
    (net (code "23") (name "/IN_6_2") (class "Default")
      (node (ref "VT16") (pin "3") (pinfunction "3_3") (pintype "passive"))
    )
    (net (code "24") (name "/IN_7_1") (class "Default")
      (node (ref "R57") (pin "2") (pinfunction "2_2") (pintype "passive"))
    )
    (net (code "25") (name "/IN_7_2") (class "Default")
      (node (ref "VT11") (pin "3") (pinfunction "3_3") (pintype "passive"))
    )
    (net (code "26") (name "/IN_8_1") (class "Default")
      (node (ref "R77") (pin "2") (pinfunction "2_2") (pintype "passive"))
    )
    (net (code "27") (name "/IN_8_2") (class "Default")
      (node (ref "VT14") (pin "3") (pinfunction "3_3") (pintype "passive"))
    )
    (net (code "28") (name "/IN_9_1") (class "Default")
      (node (ref "R93") (pin "2") (pinfunction "2_2") (pintype "passive"))
    )
    (net (code "29") (name "/IN_9_2") (class "Default")
      (node (ref "VT17") (pin "3") (pinfunction "3_3") (pintype "passive"))
    )
    (net (code "30") (name "GND") (class "Default")
      (node (ref "C10") (pin "2") (pinfunction "2_2") (pintype "passive"))
      (node (ref "C11") (pin "2") (pinfunction "2_2") (pintype "passive"))
      (node (ref "C12") (pin "2") (pinfunction "2_2") (pintype "passive"))
      (node (ref "C13") (pin "2") (pinfunction "2_2") (pintype "passive"))
      (node (ref "C14") (pin "2") (pinfunction "2_2") (pintype "passive"))
      (node (ref "C15") (pin "2") (pinfunction "2_2") (pintype "passive"))
      (node (ref "C16") (pin "2") (pinfunction "2_2") (pintype "passive"))
      (node (ref "C17") (pin "2") (pinfunction "2_2") (pintype "passive"))
      (node (ref "C9") (pin "2") (pinfunction "2_2") (pintype "passive"))
      (node (ref "DA20") (pin "5") (pinfunction "GND_5") (pintype "passive"))
      (node (ref "DA21") (pin "5") (pinfunction "GND_5") (pintype "passive"))
      (node (ref "DA22") (pin "5") (pinfunction "GND_5") (pintype "passive"))
      (node (ref "DA26") (pin "5") (pinfunction "GND_5") (pintype "passive"))
      (node (ref "DA27") (pin "5") (pinfunction "GND_5") (pintype "passive"))
      (node (ref "DA28") (pin "5") (pinfunction "GND_5") (pintype "passive"))
      (node (ref "DA32") (pin "5") (pinfunction "GND_5") (pintype "passive"))
      (node (ref "DA33") (pin "5") (pinfunction "GND_5") (pintype "passive"))
      (node (ref "DA34") (pin "5") (pinfunction "GND_5") (pintype "passive"))
    )
    (net (code "31") (name "GND_INPUTS") (class "Default")
      (node (ref "DA17") (pin "3") (pinfunction "ANODE_3") (pintype "passive"))
      (node (ref "DA18") (pin "3") (pinfunction "ANODE_3") (pintype "passive"))
      (node (ref "DA19") (pin "3") (pinfunction "ANODE_3") (pintype "passive"))
      (node (ref "DA23") (pin "3") (pinfunction "ANODE_3") (pintype "passive"))
      (node (ref "DA24") (pin "3") (pinfunction "ANODE_3") (pintype "passive"))
      (node (ref "DA25") (pin "3") (pinfunction "ANODE_3") (pintype "passive"))
      (node (ref "DA29") (pin "3") (pinfunction "ANODE_3") (pintype "passive"))
      (node (ref "DA30") (pin "3") (pinfunction "ANODE_3") (pintype "passive"))
      (node (ref "DA31") (pin "3") (pinfunction "ANODE_3") (pintype "passive"))
      (node (ref "R58") (pin "1") (pinfunction "1_1") (pintype "passive"))
      (node (ref "R59") (pin "1") (pinfunction "1_1") (pintype "passive"))
      (node (ref "R60") (pin "1") (pinfunction "1_1") (pintype "passive"))
      (node (ref "R75") (pin "1") (pinfunction "1_1") (pintype "passive"))
      (node (ref "R76") (pin "1") (pinfunction "1_1") (pintype "passive"))
      (node (ref "R78") (pin "1") (pinfunction "1_1") (pintype "passive"))
      (node (ref "R94") (pin "1") (pinfunction "1_1") (pintype "passive"))
      (node (ref "R95") (pin "1") (pinfunction "1_1") (pintype "passive"))
      (node (ref "R96") (pin "1") (pinfunction "1_1") (pintype "passive"))
    )
    (net (code "32") (name "Net-(DA17-CATHODE)") (class "Default")
      (node (ref "DA17") (pin "1") (pinfunction "CATHODE_1") (pintype "passive"))
      (node (ref "R49") (pin "1") (pinfunction "1_1") (pintype "passive"))
      (node (ref "R52") (pin "1") (pinfunction "1_1") (pintype "passive"))
    )
    (net (code "33") (name "Net-(DA17-REF)") (class "Default")
      (node (ref "DA17") (pin "2") (pinfunction "REF_2") (pintype "passive"))
      (node (ref "R58") (pin "2") (pinfunction "2_2") (pintype "passive"))
      (node (ref "VT9") (pin "2") (pinfunction "2_2") (pintype "passive"))
    )
    (net (code "34") (name "Net-(DA18-CATHODE)") (class "Default")
      (node (ref "DA18") (pin "1") (pinfunction "CATHODE_1") (pintype "passive"))
      (node (ref "R50") (pin "1") (pinfunction "1_1") (pintype "passive"))
      (node (ref "R53") (pin "1") (pinfunction "1_1") (pintype "passive"))
    )
    (net (code "35") (name "Net-(DA18-REF)") (class "Default")
      (node (ref "DA18") (pin "2") (pinfunction "REF_2") (pintype "passive"))
      (node (ref "R59") (pin "2") (pinfunction "2_2") (pintype "passive"))
      (node (ref "VT10") (pin "2") (pinfunction "2_2") (pintype "passive"))
    )
    (net (code "36") (name "Net-(DA19-CATHODE)") (class "Default")
      (node (ref "DA19") (pin "1") (pinfunction "CATHODE_1") (pintype "passive"))
      (node (ref "R51") (pin "1") (pinfunction "1_1") (pintype "passive"))
      (node (ref "R54") (pin "1") (pinfunction "1_1") (pintype "passive"))
    )
    (net (code "37") (name "Net-(DA19-REF)") (class "Default")
      (node (ref "DA19") (pin "2") (pinfunction "REF_2") (pintype "passive"))
      (node (ref "R60") (pin "2") (pinfunction "2_2") (pintype "passive"))
      (node (ref "VT11") (pin "2") (pinfunction "2_2") (pintype "passive"))
    )
    (net (code "38") (name "Net-(DA20-CATHODE)") (class "Default")
      (node (ref "DA20") (pin "2") (pinfunction "CATHODE_2") (pintype "passive"))
      (node (ref "R55") (pin "1") (pinfunction "1_1") (pintype "passive"))
    )
    (net (code "39") (name "Net-(DA20-VO)") (class "Default")
      (node (ref "DA20") (pin "4") (pinfunction "VO_4") (pintype "passive"))
      (node (ref "R62") (pin "1") (pinfunction "1_1") (pintype "passive"))
      (node (ref "R64") (pin "1") (pinfunction "1_1") (pintype "passive"))
    )
    (net (code "40") (name "Net-(DA21-CATHODE)") (class "Default")
      (node (ref "DA21") (pin "2") (pinfunction "CATHODE_2") (pintype "passive"))
      (node (ref "R56") (pin "1") (pinfunction "1_1") (pintype "passive"))
    )
    (net (code "41") (name "Net-(DA21-VO)") (class "Default")
      (node (ref "DA21") (pin "4") (pinfunction "VO_4") (pintype "passive"))
      (node (ref "R61") (pin "1") (pinfunction "1_1") (pintype "passive"))
      (node (ref "R65") (pin "1") (pinfunction "1_1") (pintype "passive"))
    )
    (net (code "42") (name "Net-(DA22-CATHODE)") (class "Default")
      (node (ref "DA22") (pin "2") (pinfunction "CATHODE_2") (pintype "passive"))
      (node (ref "R57") (pin "1") (pinfunction "1_1") (pintype "passive"))
    )
    (net (code "43") (name "Net-(DA22-VO)") (class "Default")
      (node (ref "DA22") (pin "4") (pinfunction "VO_4") (pintype "passive"))
      (node (ref "R63") (pin "1") (pinfunction "1_1") (pintype "passive"))
      (node (ref "R66") (pin "1") (pinfunction "1_1") (pintype "passive"))
    )
    (net (code "44") (name "Net-(DA23-CATHODE)") (class "Default")
      (node (ref "DA23") (pin "1") (pinfunction "CATHODE_1") (pintype "passive"))
      (node (ref "R67") (pin "1") (pinfunction "1_1") (pintype "passive"))
      (node (ref "R70") (pin "1") (pinfunction "1_1") (pintype "passive"))
    )
    (net (code "45") (name "Net-(DA23-REF)") (class "Default")
      (node (ref "DA23") (pin "2") (pinfunction "REF_2") (pintype "passive"))
      (node (ref "R75") (pin "2") (pinfunction "2_2") (pintype "passive"))
      (node (ref "VT12") (pin "2") (pinfunction "2_2") (pintype "passive"))
    )
    (net (code "46") (name "Net-(DA24-CATHODE)") (class "Default")
      (node (ref "DA24") (pin "1") (pinfunction "CATHODE_1") (pintype "passive"))
      (node (ref "R68") (pin "1") (pinfunction "1_1") (pintype "passive"))
      (node (ref "R71") (pin "1") (pinfunction "1_1") (pintype "passive"))
    )
    (net (code "47") (name "Net-(DA24-REF)") (class "Default")
      (node (ref "DA24") (pin "2") (pinfunction "REF_2") (pintype "passive"))
      (node (ref "R76") (pin "2") (pinfunction "2_2") (pintype "passive"))
      (node (ref "VT13") (pin "2") (pinfunction "2_2") (pintype "passive"))
    )
    (net (code "48") (name "Net-(DA25-CATHODE)") (class "Default")
      (node (ref "DA25") (pin "1") (pinfunction "CATHODE_1") (pintype "passive"))
      (node (ref "R69") (pin "1") (pinfunction "1_1") (pintype "passive"))
      (node (ref "R72") (pin "1") (pinfunction "1_1") (pintype "passive"))
    )
    (net (code "49") (name "Net-(DA25-REF)") (class "Default")
      (node (ref "DA25") (pin "2") (pinfunction "REF_2") (pintype "passive"))
      (node (ref "R78") (pin "2") (pinfunction "2_2") (pintype "passive"))
      (node (ref "VT14") (pin "2") (pinfunction "2_2") (pintype "passive"))
    )
    (net (code "50") (name "Net-(DA26-CATHODE)") (class "Default")
      (node (ref "DA26") (pin "2") (pinfunction "CATHODE_2") (pintype "passive"))
      (node (ref "R73") (pin "1") (pinfunction "1_1") (pintype "passive"))
    )
    (net (code "51") (name "Net-(DA26-VO)") (class "Default")
      (node (ref "DA26") (pin "4") (pinfunction "VO_4") (pintype "passive"))
      (node (ref "R79") (pin "1") (pinfunction "1_1") (pintype "passive"))
      (node (ref "R82") (pin "1") (pinfunction "1_1") (pintype "passive"))
    )
    (net (code "52") (name "Net-(DA27-CATHODE)") (class "Default")
      (node (ref "DA27") (pin "2") (pinfunction "CATHODE_2") (pintype "passive"))
      (node (ref "R74") (pin "1") (pinfunction "1_1") (pintype "passive"))
    )
    (net (code "53") (name "Net-(DA27-VO)") (class "Default")
      (node (ref "DA27") (pin "4") (pinfunction "VO_4") (pintype "passive"))
      (node (ref "R80") (pin "1") (pinfunction "1_1") (pintype "passive"))
      (node (ref "R83") (pin "1") (pinfunction "1_1") (pintype "passive"))
    )
    (net (code "54") (name "Net-(DA28-CATHODE)") (class "Default")
      (node (ref "DA28") (pin "2") (pinfunction "CATHODE_2") (pintype "passive"))
      (node (ref "R77") (pin "1") (pinfunction "1_1") (pintype "passive"))
    )
    (net (code "55") (name "Net-(DA28-VO)") (class "Default")
      (node (ref "DA28") (pin "4") (pinfunction "VO_4") (pintype "passive"))
      (node (ref "R81") (pin "1") (pinfunction "1_1") (pintype "passive"))
      (node (ref "R84") (pin "1") (pinfunction "1_1") (pintype "passive"))
    )
    (net (code "56") (name "Net-(DA29-CATHODE)") (class "Default")
      (node (ref "DA29") (pin "1") (pinfunction "CATHODE_1") (pintype "passive"))
      (node (ref "R85") (pin "1") (pinfunction "1_1") (pintype "passive"))
      (node (ref "R88") (pin "1") (pinfunction "1_1") (pintype "passive"))
    )
    (net (code "57") (name "Net-(DA29-REF)") (class "Default")
      (node (ref "DA29") (pin "2") (pinfunction "REF_2") (pintype "passive"))
      (node (ref "R94") (pin "2") (pinfunction "2_2") (pintype "passive"))
      (node (ref "VT15") (pin "2") (pinfunction "2_2") (pintype "passive"))
    )
    (net (code "58") (name "Net-(DA30-CATHODE)") (class "Default")
      (node (ref "DA30") (pin "1") (pinfunction "CATHODE_1") (pintype "passive"))
      (node (ref "R86") (pin "1") (pinfunction "1_1") (pintype "passive"))
      (node (ref "R89") (pin "1") (pinfunction "1_1") (pintype "passive"))
    )
    (net (code "59") (name "Net-(DA30-REF)") (class "Default")
      (node (ref "DA30") (pin "2") (pinfunction "REF_2") (pintype "passive"))
      (node (ref "R95") (pin "2") (pinfunction "2_2") (pintype "passive"))
      (node (ref "VT16") (pin "2") (pinfunction "2_2") (pintype "passive"))
    )
    (net (code "60") (name "Net-(DA31-CATHODE)") (class "Default")
      (node (ref "DA31") (pin "1") (pinfunction "CATHODE_1") (pintype "passive"))
      (node (ref "R87") (pin "1") (pinfunction "1_1") (pintype "passive"))
      (node (ref "R90") (pin "1") (pinfunction "1_1") (pintype "passive"))
    )
    (net (code "61") (name "Net-(DA31-REF)") (class "Default")
      (node (ref "DA31") (pin "2") (pinfunction "REF_2") (pintype "passive"))
      (node (ref "R96") (pin "2") (pinfunction "2_2") (pintype "passive"))
      (node (ref "VT17") (pin "2") (pinfunction "2_2") (pintype "passive"))
    )
    (net (code "62") (name "Net-(DA32-CATHODE)") (class "Default")
      (node (ref "DA32") (pin "2") (pinfunction "CATHODE_2") (pintype "passive"))
      (node (ref "R91") (pin "1") (pinfunction "1_1") (pintype "passive"))
    )
    (net (code "63") (name "Net-(DA32-VO)") (class "Default")
      (node (ref "DA32") (pin "4") (pinfunction "VO_4") (pintype "passive"))
      (node (ref "R102") (pin "1") (pinfunction "1_1") (pintype "passive"))
      (node (ref "R99") (pin "1") (pinfunction "1_1") (pintype "passive"))
    )
    (net (code "64") (name "Net-(DA33-CATHODE)") (class "Default")
      (node (ref "DA33") (pin "2") (pinfunction "CATHODE_2") (pintype "passive"))
      (node (ref "R92") (pin "1") (pinfunction "1_1") (pintype "passive"))
    )
    (net (code "65") (name "Net-(DA33-VO)") (class "Default")
      (node (ref "DA33") (pin "4") (pinfunction "VO_4") (pintype "passive"))
      (node (ref "R100") (pin "1") (pinfunction "1_1") (pintype "passive"))
      (node (ref "R97") (pin "1") (pinfunction "1_1") (pintype "passive"))
    )
    (net (code "66") (name "Net-(DA34-CATHODE)") (class "Default")
      (node (ref "DA34") (pin "2") (pinfunction "CATHODE_2") (pintype "passive"))
      (node (ref "R93") (pin "1") (pinfunction "1_1") (pintype "passive"))
    )
    (net (code "67") (name "Net-(DA34-VO)") (class "Default")
      (node (ref "DA34") (pin "4") (pinfunction "VO_4") (pintype "passive"))
      (node (ref "R101") (pin "1") (pinfunction "1_1") (pintype "passive"))
      (node (ref "R98") (pin "1") (pinfunction "1_1") (pintype "passive"))
    )
    (net (code "68") (name "Net-(R52-Pad2)") (class "Default")
      (node (ref "R52") (pin "2") (pinfunction "2_2") (pintype "passive"))
      (node (ref "VT9") (pin "1") (pinfunction "1_1") (pintype "passive"))
    )
    (net (code "69") (name "Net-(R53-Pad2)") (class "Default")
      (node (ref "R53") (pin "2") (pinfunction "2_2") (pintype "passive"))
      (node (ref "VT10") (pin "1") (pinfunction "1_1") (pintype "passive"))
    )
    (net (code "70") (name "Net-(R54-Pad2)") (class "Default")
      (node (ref "R54") (pin "2") (pinfunction "2_2") (pintype "passive"))
      (node (ref "VT11") (pin "1") (pinfunction "1_1") (pintype "passive"))
    )
    (net (code "71") (name "Net-(R70-Pad2)") (class "Default")
      (node (ref "R70") (pin "2") (pinfunction "2_2") (pintype "passive"))
      (node (ref "VT12") (pin "1") (pinfunction "1_1") (pintype "passive"))
    )
    (net (code "72") (name "Net-(R71-Pad2)") (class "Default")
      (node (ref "R71") (pin "2") (pinfunction "2_2") (pintype "passive"))
      (node (ref "VT13") (pin "1") (pinfunction "1_1") (pintype "passive"))
    )
    (net (code "73") (name "Net-(R72-Pad2)") (class "Default")
      (node (ref "R72") (pin "2") (pinfunction "2_2") (pintype "passive"))
      (node (ref "VT14") (pin "1") (pinfunction "1_1") (pintype "passive"))
    )
    (net (code "74") (name "Net-(R88-Pad2)") (class "Default")
      (node (ref "R88") (pin "2") (pinfunction "2_2") (pintype "passive"))
      (node (ref "VT15") (pin "1") (pinfunction "1_1") (pintype "passive"))
    )
    (net (code "75") (name "Net-(R89-Pad2)") (class "Default")
      (node (ref "R89") (pin "2") (pinfunction "2_2") (pintype "passive"))
      (node (ref "VT16") (pin "1") (pinfunction "1_1") (pintype "passive"))
    )
    (net (code "76") (name "Net-(R90-Pad2)") (class "Default")
      (node (ref "R90") (pin "2") (pinfunction "2_2") (pintype "passive"))
      (node (ref "VT17") (pin "1") (pinfunction "1_1") (pintype "passive"))
    )
    (net (code "77") (name "unconnected-(DA20-NC-Pad3)") (class "Default")
      (node (ref "DA20") (pin "3") (pinfunction "NC_3") (pintype "passive+no_connect"))
    )
    (net (code "78") (name "unconnected-(DA21-NC-Pad3)") (class "Default")
      (node (ref "DA21") (pin "3") (pinfunction "NC_3") (pintype "passive+no_connect"))
    )
    (net (code "79") (name "unconnected-(DA22-NC-Pad3)") (class "Default")
      (node (ref "DA22") (pin "3") (pinfunction "NC_3") (pintype "passive+no_connect"))
    )
    (net (code "80") (name "unconnected-(DA26-NC-Pad3)") (class "Default")
      (node (ref "DA26") (pin "3") (pinfunction "NC_3") (pintype "passive+no_connect"))
    )
    (net (code "81") (name "unconnected-(DA27-NC-Pad3)") (class "Default")
      (node (ref "DA27") (pin "3") (pinfunction "NC_3") (pintype "passive+no_connect"))
    )
    (net (code "82") (name "unconnected-(DA28-NC-Pad3)") (class "Default")
      (node (ref "DA28") (pin "3") (pinfunction "NC_3") (pintype "passive+no_connect"))
    )
    (net (code "83") (name "unconnected-(DA32-NC-Pad3)") (class "Default")
      (node (ref "DA32") (pin "3") (pinfunction "NC_3") (pintype "passive+no_connect"))
    )
    (net (code "84") (name "unconnected-(DA33-NC-Pad3)") (class "Default")
      (node (ref "DA33") (pin "3") (pinfunction "NC_3") (pintype "passive+no_connect"))
    )
    (net (code "85") (name "unconnected-(DA34-NC-Pad3)") (class "Default")
      (node (ref "DA34") (pin "3") (pinfunction "NC_3") (pintype "passive+no_connect"))
    )
  )
)
